# Gamecube.net
KiCad netlist of a schematic drawn in EAGLE
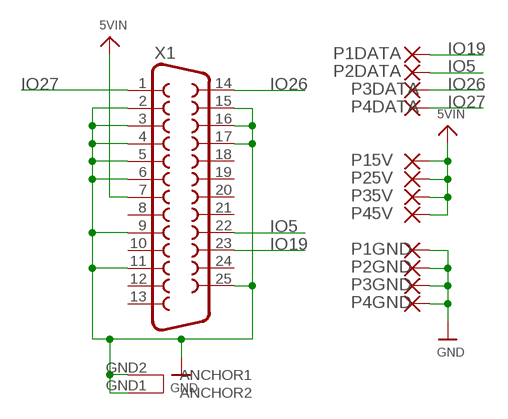
[diagram p0: schematic, sheet 1]

(export (version "E")
  (design (tool "Eeschema 10.0.6"))
  (components
    (comp (ref "P1DATA")
      (value "SMD5")
      (footprint "eagle-import:SMD2,54-5,08")
      (libsource (lib "eagle-import") (part "SMD5"))
    )
    (comp (ref "P1GND")
      (value "SMD5")
      (footprint "eagle-import:SMD2,54-5,08")
      (libsource (lib "eagle-import") (part "SMD5"))
    )
    (comp (ref "P2DATA")
      (value "SMD5")
      (footprint "eagle-import:SMD2,54-5,08")
      (libsource (lib "eagle-import") (part "SMD5"))
    )
    (comp (ref "P2GND")
      (value "SMD5")
      (footprint "eagle-import:SMD2,54-5,08")
      (libsource (lib "eagle-import") (part "SMD5"))
    )
    (comp (ref "P3DATA")
      (value "SMD5")
      (footprint "eagle-import:SMD2,54-5,08")
      (libsource (lib "eagle-import") (part "SMD5"))
    )
    (comp (ref "P3GND")
      (value "SMD5")
      (footprint "eagle-import:SMD2,54-5,08")
      (libsource (lib "eagle-import") (part "SMD5"))
    )
    (comp (ref "P4DATA")
      (value "SMD5")
      (footprint "eagle-import:SMD2,54-5,08")
      (libsource (lib "eagle-import") (part "SMD5"))
    )
    (comp (ref "P4GND")
      (value "SMD5")
      (footprint "eagle-import:SMD2,54-5,08")
      (libsource (lib "eagle-import") (part "SMD5"))
    )
    (comp (ref "P15V")
      (value "SMD5")
      (footprint "eagle-import:SMD2,54-5,08")
      (libsource (lib "eagle-import") (part "SMD5"))
    )
    (comp (ref "P25V")
      (value "SMD5")
      (footprint "eagle-import:SMD2,54-5,08")
      (libsource (lib "eagle-import") (part "SMD5"))
    )
    (comp (ref "P35V")
      (value "SMD5")
      (footprint "eagle-import:SMD2,54-5,08")
      (libsource (lib "eagle-import") (part "SMD5"))
    )
    (comp (ref "P45V")
      (value "SMD5")
      (footprint "eagle-import:SMD2,54-5,08")
      (libsource (lib "eagle-import") (part "SMD5"))
    )
    (comp (ref "X1")
      (value "DB25_FEMALEHP")
      (footprint "eagle-import:F25HP")
      (libsource (lib "eagle-import") (part "DB25_FEMALEHP"))
    )
  )
  (nets
    (net (code "1") (name "/IO5") (class "Default")
      (node (ref "P2DATA") (pin "1") (pinfunction "P_1") (pintype "passive"))
      (node (ref "X1") (pin "22") (pinfunction "22_22") (pintype "passive"))
    )
    (net (code "2") (name "/IO19") (class "Default")
      (node (ref "P1DATA") (pin "1") (pinfunction "P_1") (pintype "passive"))
      (node (ref "X1") (pin "23") (pinfunction "23_23") (pintype "passive"))
    )
    (net (code "3") (name "/IO26") (class "Default")
      (node (ref "P3DATA") (pin "1") (pinfunction "P_1") (pintype "passive"))
      (node (ref "X1") (pin "14") (pinfunction "14_14") (pintype "passive"))
    )
    (net (code "4") (name "/IO27") (class "Default")
      (node (ref "P4DATA") (pin "1") (pinfunction "P_1") (pintype "passive"))
      (node (ref "X1") (pin "1") (pinfunction "1_1") (pintype "passive"))
    )
    (net (code "5") (name "5VIN") (class "Default")
      (node (ref "P15V") (pin "1") (pinfunction "P_1") (pintype "passive"))
      (node (ref "P25V") (pin "1") (pinfunction "P_1") (pintype "passive"))
      (node (ref "P35V") (pin "1") (pinfunction "P_1") (pintype "passive"))
      (node (ref "P45V") (pin "1") (pinfunction "P_1") (pintype "passive"))
      (node (ref "X1") (pin "7") (pinfunction "7_7") (pintype "passive"))
    )
    (net (code "6") (name "GND") (class "Default")
      (node (ref "P1GND") (pin "1") (pinfunction "P_1") (pintype "passive"))
      (node (ref "P2GND") (pin "1") (pinfunction "P_1") (pintype "passive"))
      (node (ref "P3GND") (pin "1") (pinfunction "P_1") (pintype "passive"))
      (node (ref "P4GND") (pin "1") (pinfunction "P_1") (pintype "passive"))
      (node (ref "X1") (pin "11") (pinfunction "11_11") (pintype "passive"))
      (node (ref "X1") (pin "15") (pinfunction "15_15") (pintype "passive"))
      (node (ref "X1") (pin "16") (pinfunction "16_16") (pintype "passive"))
      (node (ref "X1") (pin "17") (pinfunction "17_17") (pintype "passive"))
      (node (ref "X1") (pin "2") (pinfunction "2_2") (pintype "passive"))
      (node (ref "X1") (pin "25") (pinfunction "25_25") (pintype "passive"))
      (node (ref "X1") (pin "3") (pinfunction "3_3") (pintype "passive"))
      (node (ref "X1") (pin "4") (pinfunction "4_4") (pintype "passive"))
      (node (ref "X1") (pin "5") (pinfunction "5_5") (pintype "passive"))
      (node (ref "X1") (pin "6") (pinfunction "6_6") (pintype "passive"))
      (node (ref "X1") (pin "9") (pinfunction "9_9") (pintype "passive"))
      (node (ref "X1") (pin "GND1") (pinfunction "ANCHOR2_GND1") (pintype "bidirectional"))
      (node (ref "X1") (pin "GND2") (pinfunction "ANCHOR1_GND2") (pintype "bidirectional"))
    )
    (net (code "7") (name "unconnected-(X1-Pad8)") (class "Default")
      (node (ref "X1") (pin "8") (pinfunction "8_8") (pintype "passive"))
    )
    (net (code "8") (name "unconnected-(X1-Pad10)") (class "Default")
      (node (ref "X1") (pin "10") (pinfunction "10_10") (pintype "passive"))
    )
    (net (code "9") (name "unconnected-(X1-Pad12)") (class "Default")
      (node (ref "X1") (pin "12") (pinfunction "12_12") (pintype "passive"))
    )
    (net (code "10") (name "unconnected-(X1-Pad13)") (class "Default")
      (node (ref "X1") (pin "13") (pinfunction "13_13") (pintype "passive"))
    )
    (net (code "11") (name "unconnected-(X1-Pad18)") (class "Default")
      (node (ref "X1") (pin "18") (pinfunction "18_18") (pintype "passive"))
    )
    (net (code "12") (name "unconnected-(X1-Pad19)") (class "Default")
      (node (ref "X1") (pin "19") (pinfunction "19_19") (pintype "passive"))
    )
    (net (code "13") (name "unconnected-(X1-Pad20)") (class "Default")
      (node (ref "X1") (pin "20") (pinfunction "20_20") (pintype "passive"))
    )
    (net (code "14") (name "unconnected-(X1-Pad21)") (class "Default")
      (node (ref "X1") (pin "21") (pinfunction "21_21") (pintype "passive"))
    )
    (net (code "15") (name "unconnected-(X1-Pad24)") (class "Default")
      (node (ref "X1") (pin "24") (pinfunction "24_24") (pintype "passive"))
    )
  )
)
